# SparkX_EZ_ARTIC_R2.net
KiCad netlist of a schematic drawn in EAGLE
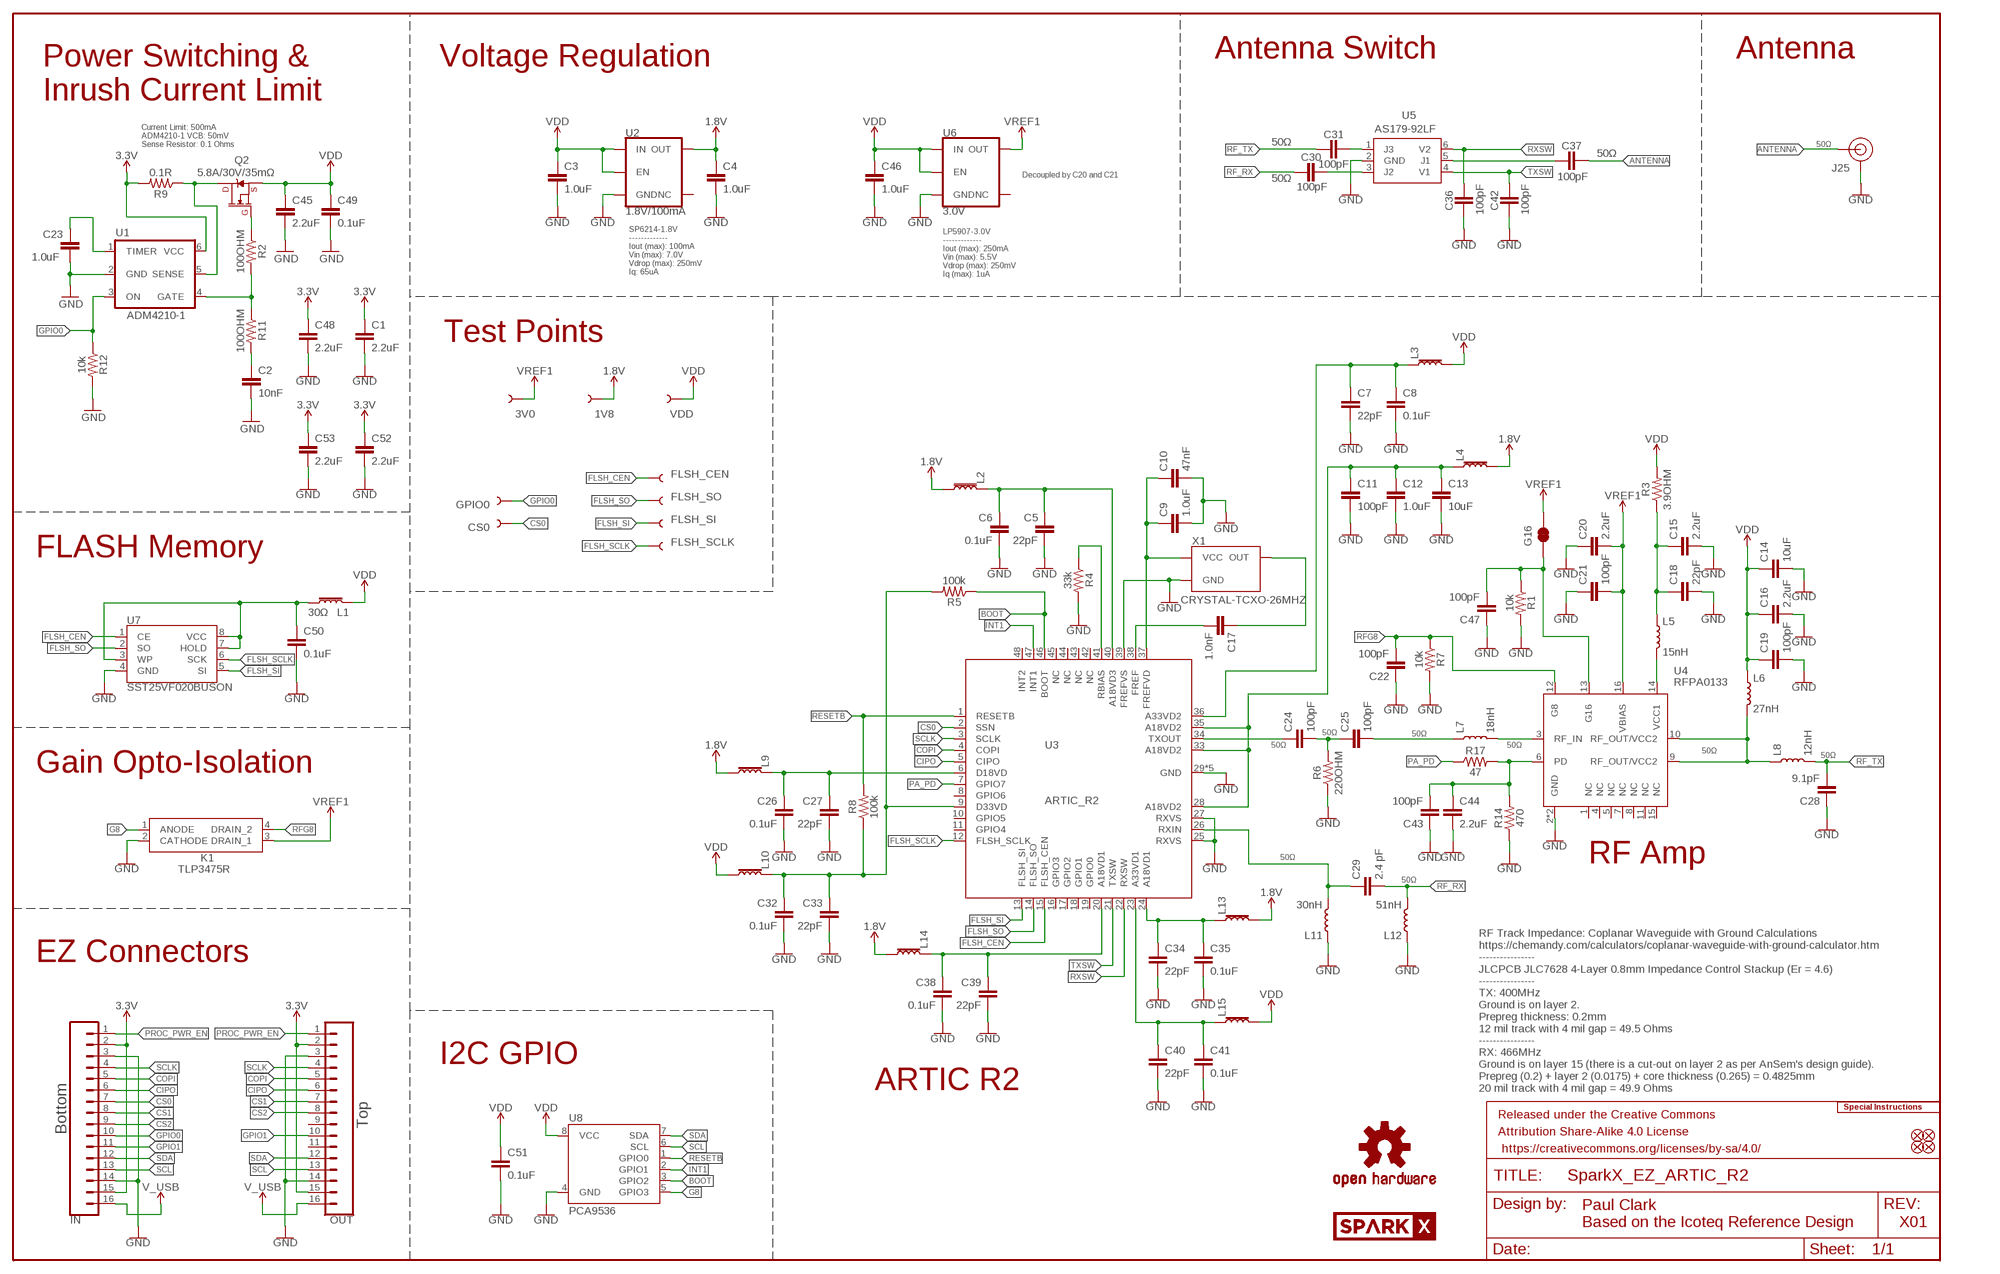
[diagram p0: schematic, sheet 1]

(export (version "E")
  (design (tool "Eeschema 10.0.6"))
  (components
    (comp (ref "1V8")
      (value "TEST-POINT3")
      (footprint "eagle-import:PAD.03X.03")
      (libsource (lib "eagle-import") (part "TEST-POINT3"))
    )
    (comp (ref "3V0")
      (value "TEST-POINT3")
      (footprint "eagle-import:PAD.03X.03")
      (libsource (lib "eagle-import") (part "TEST-POINT3"))
    )
    (comp (ref "C1")
      (value "2.2uF")
      (footprint "eagle-import:0402-TIGHT")
      (libsource (lib "eagle-import") (part "2.2UF-0402_TIGHT-10V-10%-X5R"))
    )
    (comp (ref "C2")
      (value "10nF")
      (footprint "eagle-import:0402-TIGHT")
      (libsource (lib "eagle-import") (part "10NF-0402T-25V-10%"))
    )
    (comp (ref "C3")
      (value "1.0uF")
      (footprint "eagle-import:0402-TIGHT")
      (libsource (lib "eagle-import") (part "1.0UF-0402T-16V-10%"))
    )
    (comp (ref "C4")
      (value "1.0uF")
      (footprint "eagle-import:0402-TIGHT")
      (libsource (lib "eagle-import") (part "1.0UF-0402T-16V-10%"))
    )
    (comp (ref "C5")
      (value "22pF")
      (footprint "eagle-import:0402-TIGHT")
      (libsource (lib "eagle-import") (part "22PF-0402T-16V-10%"))
    )
    (comp (ref "C6")
      (value "0.1uF")
      (footprint "eagle-import:0402-TIGHT")
      (libsource (lib "eagle-import") (part "0.1UF-0402T-6.3V-10%-X7R"))
    )
    (comp (ref "C7")
      (value "22pF")
      (footprint "eagle-import:0402-TIGHT")
      (libsource (lib "eagle-import") (part "22PF-0402T-16V-10%"))
    )
    (comp (ref "C8")
      (value "0.1uF")
      (footprint "eagle-import:0402-TIGHT")
      (libsource (lib "eagle-import") (part "0.1UF-0402T-6.3V-10%-X7R"))
    )
    (comp (ref "C9")
      (value "1.0uF")
      (footprint "eagle-import:0402-TIGHT")
      (libsource (lib "eagle-import") (part "1.0UF-0402T-16V-10%"))
    )
    (comp (ref "C10")
      (value "47nF")
      (footprint "eagle-import:0402-TIGHT")
      (libsource (lib "eagle-import") (part "47NF-0402_TIGHT-25V-10%-X7R"))
    )
    (comp (ref "C11")
      (value "100pF")
      (footprint "eagle-import:0402-TIGHT")
      (libsource (lib "eagle-import") (part "100PF-0402T-50V-5%"))
    )
    (comp (ref "C12")
      (value "1.0uF")
      (footprint "eagle-import:0402-TIGHT")
      (libsource (lib "eagle-import") (part "1.0UF-0402T-16V-10%"))
    )
    (comp (ref "C13")
      (value "10uF")
      (footprint "eagle-import:0402-TIGHT")
      (libsource (lib "eagle-import") (part "10UF-0402T-6.3V-20%"))
    )
    (comp (ref "C14")
      (value "10uF")
      (footprint "eagle-import:0402-TIGHT")
      (libsource (lib "eagle-import") (part "10UF-0402T-6.3V-20%"))
    )
    (comp (ref "C15")
      (value "2.2uF")
      (footprint "eagle-import:0402-TIGHT")
      (libsource (lib "eagle-import") (part "2.2UF-0402_TIGHT-10V-10%-X5R"))
    )
    (comp (ref "C16")
      (value "2.2uF")
      (footprint "eagle-import:0402-TIGHT")
      (libsource (lib "eagle-import") (part "2.2UF-0402_TIGHT-10V-10%-X5R"))
    )
    (comp (ref "C17")
      (value "1.0nF")
      (footprint "eagle-import:0402-TIGHT")
      (libsource (lib "eagle-import") (part "1.0NF/1000PF-0402_TIGHT-50V-10%"))
    )
    (comp (ref "C18")
      (value "22pF")
      (footprint "eagle-import:0402-TIGHT")
      (libsource (lib "eagle-import") (part "22PF-0402T-16V-10%"))
    )
    (comp (ref "C19")
      (value "100pF")
      (footprint "eagle-import:0402-TIGHT")
      (libsource (lib "eagle-import") (part "100PF-0402T-50V-5%"))
    )
    (comp (ref "C20")
      (value "2.2uF")
      (footprint "eagle-import:0402-TIGHT")
      (libsource (lib "eagle-import") (part "2.2UF-0402_TIGHT-10V-10%-X5R"))
    )
    (comp (ref "C21")
      (value "100pF")
      (footprint "eagle-import:0402-TIGHT")
      (libsource (lib "eagle-import") (part "100PF-0402T-50V-5%"))
    )
    (comp (ref "C22")
      (value "100pF")
      (footprint "eagle-import:0402-TIGHT")
      (libsource (lib "eagle-import") (part "100PF-0402T-50V-5%"))
    )
    (comp (ref "C23")
      (value "1.0uF")
      (footprint "eagle-import:0402-TIGHT")
      (libsource (lib "eagle-import") (part "1.0UF-0402T-16V-10%"))
    )
    (comp (ref "C24")
      (value "100pF")
      (footprint "eagle-import:0402-TIGHT")
      (libsource (lib "eagle-import") (part "100PF-0402T-50V-5%"))
    )
    (comp (ref "C25")
      (value "100pF")
      (footprint "eagle-import:0402-TIGHT")
      (libsource (lib "eagle-import") (part "100PF-0402T-50V-5%"))
    )
    (comp (ref "C26")
      (value "0.1uF")
      (footprint "eagle-import:0402-TIGHT")
      (libsource (lib "eagle-import") (part "0.1UF-0402T-6.3V-10%-X7R"))
    )
    (comp (ref "C27")
      (value "22pF")
      (footprint "eagle-import:0402-TIGHT")
      (libsource (lib "eagle-import") (part "22PF-0402T-16V-10%"))
    )
    (comp (ref "C28")
      (value "9.1pF")
      (footprint "eagle-import:0402-TIGHT")
      (fields (field (name "MOUSER_PART") "609-500R07S9R1CV4T"))
      (libsource (lib "eagle-import") (part "9.1PF-0402-TIGHT"))
    )
    (comp (ref "C29")
      (value "2.4 pF")
      (footprint "eagle-import:0402_MURATA")
      (libsource (lib "eagle-import") (part "2.4PF-0402"))
    )
    (comp (ref "C30")
      (value "100pF")
      (footprint "eagle-import:0402-TIGHT")
      (libsource (lib "eagle-import") (part "100PF-0402T-50V-5%"))
    )
    (comp (ref "C31")
      (value "100pF")
      (footprint "eagle-import:0402-TIGHT")
      (libsource (lib "eagle-import") (part "100PF-0402T-50V-5%"))
    )
    (comp (ref "C32")
      (value "0.1uF")
      (footprint "eagle-import:0402-TIGHT")
      (libsource (lib "eagle-import") (part "0.1UF-0402T-6.3V-10%-X7R"))
    )
    (comp (ref "C33")
      (value "22pF")
      (footprint "eagle-import:0402-TIGHT")
      (libsource (lib "eagle-import") (part "22PF-0402T-16V-10%"))
    )
    (comp (ref "C34")
      (value "22pF")
      (footprint "eagle-import:0402-TIGHT")
      (libsource (lib "eagle-import") (part "22PF-0402T-16V-10%"))
    )
    (comp (ref "C35")
      (value "0.1uF")
      (footprint "eagle-import:0402-TIGHT")
      (libsource (lib "eagle-import") (part "0.1UF-0402T-6.3V-10%-X7R"))
    )
    (comp (ref "C36")
      (value "100pF")
      (footprint "eagle-import:0402-TIGHT")
      (libsource (lib "eagle-import") (part "100PF-0402T-50V-5%"))
    )
    (comp (ref "C37")
      (value "100pF")
      (footprint "eagle-import:0402-TIGHT")
      (libsource (lib "eagle-import") (part "100PF-0402T-50V-5%"))
    )
    (comp (ref "C38")
      (value "0.1uF")
      (footprint "eagle-import:0402-TIGHT")
      (libsource (lib "eagle-import") (part "0.1UF-0402T-6.3V-10%-X7R"))
    )
    (comp (ref "C39")
      (value "22pF")
      (footprint "eagle-import:0402-TIGHT")
      (libsource (lib "eagle-import") (part "22PF-0402T-16V-10%"))
    )
    (comp (ref "C40")
      (value "22pF")
      (footprint "eagle-import:0402-TIGHT")
      (libsource (lib "eagle-import") (part "22PF-0402T-16V-10%"))
    )
    (comp (ref "C41")
      (value "0.1uF")
      (footprint "eagle-import:0402-TIGHT")
      (libsource (lib "eagle-import") (part "0.1UF-0402T-6.3V-10%-X7R"))
    )
    (comp (ref "C42")
      (value "100pF")
      (footprint "eagle-import:0402-TIGHT")
      (libsource (lib "eagle-import") (part "100PF-0402T-50V-5%"))
    )
    (comp (ref "C43")
      (value "100pF")
      (footprint "eagle-import:0402-TIGHT")
      (libsource (lib "eagle-import") (part "100PF-0402T-50V-5%"))
    )
    (comp (ref "C44")
      (value "2.2uF")
      (footprint "eagle-import:0402-TIGHT")
      (libsource (lib "eagle-import") (part "2.2UF-0402_TIGHT-10V-10%-X5R"))
    )
    (comp (ref "C45")
      (value "2.2uF")
      (footprint "eagle-import:0402-TIGHT")
      (libsource (lib "eagle-import") (part "2.2UF-0402_TIGHT-10V-10%-X5R"))
    )
    (comp (ref "C46")
      (value "1.0uF")
      (footprint "eagle-import:0402-TIGHT")
      (libsource (lib "eagle-import") (part "1.0UF-0402T-16V-10%"))
    )
    (comp (ref "C47")
      (value "100pF")
      (footprint "eagle-import:0402-TIGHT")
      (libsource (lib "eagle-import") (part "100PF-0402T-50V-5%"))
    )
    (comp (ref "C48")
      (value "2.2uF")
      (footprint "eagle-import:0402-TIGHT")
      (libsource (lib "eagle-import") (part "2.2UF-0402_TIGHT-10V-10%-X5R"))
    )
    (comp (ref "C49")
      (value "0.1uF")
      (footprint "eagle-import:0402-TIGHT")
      (libsource (lib "eagle-import") (part "0.1UF-0402T-10V-10%-X7R"))
    )
    (comp (ref "C50")
      (value "0.1uF")
      (footprint "eagle-import:0402-TIGHT")
      (libsource (lib "eagle-import") (part "0.1UF-0402T-6.3V-10%-X7R"))
    )
    (comp (ref "C51")
      (value "0.1uF")
      (footprint "eagle-import:0402-TIGHT")
      (libsource (lib "eagle-import") (part "0.1UF-0402T-10V-10%-X7R"))
    )
    (comp (ref "C52")
      (value "2.2uF")
      (footprint "eagle-import:0402-TIGHT")
      (libsource (lib "eagle-import") (part "2.2UF-0402_TIGHT-10V-10%-X5R"))
    )
    (comp (ref "C53")
      (value "2.2uF")
      (footprint "eagle-import:0402-TIGHT")
      (libsource (lib "eagle-import") (part "2.2UF-0402_TIGHT-10V-10%-X5R"))
    )
    (comp (ref "CS0")
      (value "TEST-POINT3")
      (footprint "eagle-import:PAD.03X.03")
      (libsource (lib "eagle-import") (part "TEST-POINT3"))
    )
    (comp (ref "FD1")
      (value "FIDUCIALUFIDUCIAL")
      (footprint "eagle-import:FIDUCIAL-MICRO")
      (libsource (lib "eagle-import") (part "FIDUCIALUFIDUCIAL"))
    )
    (comp (ref "FD2")
      (value "FIDUCIALUFIDUCIAL")
      (footprint "eagle-import:FIDUCIAL-MICRO")
      (libsource (lib "eagle-import") (part "FIDUCIALUFIDUCIAL"))
    )
    (comp (ref "FD3")
      (value "FIDUCIALUFIDUCIAL")
      (footprint "eagle-import:FIDUCIAL-MICRO")
      (libsource (lib "eagle-import") (part "FIDUCIALUFIDUCIAL"))
    )
    (comp (ref "FD4")
      (value "FIDUCIALUFIDUCIAL")
      (footprint "eagle-import:FIDUCIAL-MICRO")
      (libsource (lib "eagle-import") (part "FIDUCIALUFIDUCIAL"))
    )
    (comp (ref "FLSH_CEN")
      (value "TEST-POINT3")
      (footprint "eagle-import:PAD.03X.03")
      (libsource (lib "eagle-import") (part "TEST-POINT3"))
    )
    (comp (ref "FLSH_SCLK")
      (value "TEST-POINT3")
      (footprint "eagle-import:PAD.03X.03")
      (libsource (lib "eagle-import") (part "TEST-POINT3"))
    )
    (comp (ref "FLSH_SI")
      (value "TEST-POINT3")
      (footprint "eagle-import:PAD.03X.03")
      (libsource (lib "eagle-import") (part "TEST-POINT3"))
    )
    (comp (ref "FLSH_SO")
      (value "TEST-POINT3")
      (footprint "eagle-import:PAD.03X.03")
      (libsource (lib "eagle-import") (part "TEST-POINT3"))
    )
    (comp (ref "FRAME1")
      (value "FRAME-LEDGER")
      (footprint "eagle-import:CREATIVE_COMMONS")
      (libsource (lib "eagle-import") (part "FRAME-LEDGER"))
    )
    (comp (ref "G16")
      (value "JUMPER-SMT_2_NC_TRACE_NO-SILK")
      (footprint "eagle-import:SMT-JUMPER_2_NC_TRACE_NO-SILK")
      (libsource (lib "eagle-import") (part "JUMPER-SMT_2_NC_TRACE_NO-SILK"))
    )
    (comp (ref "GPIO0")
      (value "TEST-POINT3")
      (footprint "eagle-import:PAD.03X.03")
      (libsource (lib "eagle-import") (part "TEST-POINT3"))
    )
    (comp (ref "IN")
      (value "CONN_16FPC_16_0.5MM")
      (footprint "eagle-import:FPC_16_0.5MM")
      (libsource (lib "eagle-import") (part "CONN_16FPC_16_0.5MM"))
    )
    (comp (ref "J25")
      (value "U.FL")
      (footprint "eagle-import:U.FL_REDUCED_FOOTPRINT")
      (libsource (lib "eagle-import") (part "U.FL2PIN_REDUCED_FOOTPRINT"))
    )
    (comp (ref "K1")
      (value "TLP3475R")
      (footprint "eagle-import:TLP3475RTPF")
      (fields
        (field (name "DIGIKEY_PART") "TLP3475R(TPFCT-ND - Cut Tape (CT)")
        (field (name "MOUSER_PART_NUMBER") "757-TLP3475RTPF")
      )
      (libsource (lib "eagle-import") (part "TLP3475R"))
    )
    (comp (ref "L1")
      (value "30Ω")
      (footprint "eagle-import:0402-TIGHT")
      (libsource (lib "eagle-import") (part "FERRITE_BEAD-0402-30OHM-100MHZ"))
    )
    (comp (ref "L2")
      (value "30Ω")
      (footprint "eagle-import:0402-TIGHT")
      (libsource (lib "eagle-import") (part "FERRITE_BEAD-0402-30OHM-100MHZ"))
    )
    (comp (ref "L3")
      (value "30Ω")
      (footprint "eagle-import:0402-TIGHT")
      (libsource (lib "eagle-import") (part "FERRITE_BEAD-0402-30OHM-100MHZ"))
    )
    (comp (ref "L4")
      (value "30Ω")
      (footprint "eagle-import:0402-TIGHT")
      (libsource (lib "eagle-import") (part "FERRITE_BEAD-0402-30OHM-100MHZ"))
    )
    (comp (ref "L5")
      (value "15nH")
      (footprint "eagle-import:0402_COILCRAFT")
      (fields (field (name "MOUSER_PART") "994-0402HP-15NXGLU"))
      (libsource (lib "eagle-import") (part "15NH-0402"))
    )
    (comp (ref "L6")
      (value "27nH")
      (footprint "eagle-import:0402_COILCRAFT")
      (fields (field (name "MOUSER_PART") "994-0402HP-27NXGLU"))
      (libsource (lib "eagle-import") (part "27NH-0402"))
    )
    (comp (ref "L7")
      (value "18nH")
      (footprint "eagle-import:0402_COILCRAFT")
      (fields (field (name "MOUSER_PART") "994-0402HP-18NXGLU"))
      (libsource (lib "eagle-import") (part "18NH-0402"))
    )
    (comp (ref "L8")
      (value "12nH")
      (footprint "eagle-import:0402_COILCRAFT")
      (fields (field (name "MOUSER_PART") "994-0402HP-12NXGLU"))
      (libsource (lib "eagle-import") (part "12NH-0402"))
    )
    (comp (ref "L9")
      (value "30Ω")
      (footprint "eagle-import:0402-TIGHT")
      (libsource (lib "eagle-import") (part "FERRITE_BEAD-0402-30OHM-100MHZ"))
    )
    (comp (ref "L10")
      (value "30Ω")
      (footprint "eagle-import:0402-TIGHT")
      (libsource (lib "eagle-import") (part "FERRITE_BEAD-0402-30OHM-100MHZ"))
    )
    (comp (ref "L11")
      (value "30nH")
      (footprint "eagle-import:0402_COILCRAFT")
      (fields (field (name "MOUSER_PART") "994-0402HP-30NXGLU"))
      (libsource (lib "eagle-import") (part "30NH-0402"))
    )
    (comp (ref "L12")
      (value "51nH")
      (footprint "eagle-import:0402_COILCRAFT")
      (fields (field (name "MOUSER_PART") "994-0402HP-51NXGLU"))
      (libsource (lib "eagle-import") (part "51NH-0402"))
    )
    (comp (ref "L13")
      (value "30Ω")
      (footprint "eagle-import:0402-TIGHT")
      (libsource (lib "eagle-import") (part "FERRITE_BEAD-0402-30OHM-100MHZ"))
    )
    (comp (ref "L14")
      (value "30Ω")
      (footprint "eagle-import:0402-TIGHT")
      (libsource (lib "eagle-import") (part "FERRITE_BEAD-0402-30OHM-100MHZ"))
    )
    (comp (ref "L15")
      (value "30Ω")
      (footprint "eagle-import:0402-TIGHT")
      (libsource (lib "eagle-import") (part "FERRITE_BEAD-0402-30OHM-100MHZ"))
    )
    (comp (ref "LOGO1")
      (value "SPECIAL_INSTRUCTIONS-ORDERING")
      (footprint "eagle-import:ORDERING_INSTRUCTIONS")
      (libsource (lib "eagle-import") (part "SPECIAL_INSTRUCTIONS-ORDERING"))
    )
    (comp (ref "LOGO2")
      (value "OSHW-LOGOMINI")
      (footprint "eagle-import:OSHW-LOGO-MINI")
      (libsource (lib "eagle-import") (part "OSHW-LOGOMINI"))
    )
    (comp (ref "LOGO3")
      (value "OSHW-LOGOMINI")
      (footprint "eagle-import:OSHW-LOGO-MINI")
      (libsource (lib "eagle-import") (part "OSHW-LOGOMINI"))
    )
    (comp (ref "OUT")
      (value "CONN_16FPC_16_0.5MM")
      (footprint "eagle-import:FPC_16_0.5MM")
      (libsource (lib "eagle-import") (part "CONN_16FPC_16_0.5MM"))
    )
    (comp (ref "Q2")
      (value "5.8A/30V/35mΩ")
      (footprint "eagle-import:SOT23-3")
      (libsource (lib "eagle-import") (part "MOSFET-NCH-AO3404A"))
    )
    (comp (ref "R1")
      (value "10k")
      (footprint "eagle-import:0402-TIGHT")
      (libsource (lib "eagle-import") (part "10KOHM-0402T-1/16W-1%"))
    )
    (comp (ref "R2")
      (value "100OHM")
      (footprint "eagle-import:0402-TIGHT")
      (libsource (lib "eagle-import") (part "100OHM"))
    )
    (comp (ref "R3")
      (value "3.9OHM")
      (footprint "eagle-import:0402-TIGHT")
      (fields (field (name "MOUSER_PART") "603-RC0402FR-073R9L"))
      (libsource (lib "eagle-import") (part "3.9OHM"))
    )
    (comp (ref "R4")
      (value "33k")
      (footprint "eagle-import:0402-TIGHT")
      (libsource (lib "eagle-import") (part "33KOHM-0402T-1/16W-1%"))
    )
    (comp (ref "R5")
      (value "100k")
      (footprint "eagle-import:0402-TIGHT")
      (libsource (lib "eagle-import") (part "100KOHM-0402T-1/16W-1%"))
    )
    (comp (ref "R6")
      (value "220OHM")
      (footprint "eagle-import:0402-TIGHT")
      (fields (field (name "MOUSER_PART") "755-SFR01MZPF2200"))
      (libsource (lib "eagle-import") (part "220OHM"))
    )
    (comp (ref "R7")
      (value "10k")
      (footprint "eagle-import:0402-TIGHT")
      (libsource (lib "eagle-import") (part "10KOHM-0402T-1/16W-1%"))
    )
    (comp (ref "R8")
      (value "100k")
      (footprint "eagle-import:0402-TIGHT")
      (libsource (lib "eagle-import") (part "100KOHM-0402T-1/16W-1%"))
    )
    (comp (ref "R9")
      (value "0.1R")
      (footprint "eagle-import:0603")
      (fields (field (name "DIGIKEY_PART") "P17478CT-ND") (field (name "MANUFACTURER_PART") "ERJ-3BWFR100V"))
      (libsource (lib "eagle-import") (part "RESISTOR_0603_100MILLIOHM0603"))
    )
    (comp (ref "R11")
      (value "100OHM")
      (footprint "eagle-import:0402-TIGHT")
      (libsource (lib "eagle-import") (part "100OHM"))
    )
    (comp (ref "R12")
      (value "10k")
      (footprint "eagle-import:0402-TIGHT")
      (libsource (lib "eagle-import") (part "10KOHM-0402T-1/16W-1%"))
    )
    (comp (ref "R14")
      (value "470")
      (footprint "eagle-import:0402-TIGHT")
      (libsource (lib "eagle-import") (part "470OHM-0402-TIGHT-1/16W-1%"))
    )
    (comp (ref "R17")
      (value "47")
      (footprint "eagle-import:0402-TIGHT")
      (libsource (lib "eagle-import") (part "47OHM-0402-TIGHT-1/16W-1%"))
    )
    (comp (ref "U$4")
      (value "SPARKX-LOGO3")
      (footprint "eagle-import:SPARKX-SMALL")
      (libsource (lib "eagle-import") (part "SPARKX-LOGO3"))
    )
    (comp (ref "U$8")
      (value "SPARKX-LOGO2")
      (footprint "eagle-import:SPARKX-TINY")
      (libsource (lib "eagle-import") (part "SPARKX-LOGO2"))
    )
    (comp (ref "U1")
      (value "ADM4210-1")
      (footprint "eagle-import:TSOT6")
      (libsource (lib "eagle-import") (part "ADM4210-1"))
    )
    (comp (ref "U2")
      (value "1.8V/100mA")
      (footprint "eagle-import:SC70")
      (libsource (lib "eagle-import") (part "V_REG_SP6214-1.8V"))
    )
    (comp (ref "U3")
      (value "ARTIC_R2")
      (footprint "eagle-import:QFN-48")
      (libsource (lib "eagle-import") (part "ARTIC_R2"))
    )
    (comp (ref "U4")
      (value "RFPA0133")
      (footprint "eagle-import:QFN50P300X300X86-17N")
      (fields
        (field (name "MANUFACTURER_PART_NUMBER") "RFPA0133TR7")
        (field (name "MOUSER_PART_NUMBER") "772-RFPA0133")
      )
      (libsource (lib "eagle-import") (part "RFPA0133"))
    )
    (comp (ref "U5")
      (value "AS179-92LF")
      (footprint "eagle-import:SOT65P220X100-6N")
      (libsource (lib "eagle-import") (part "AS179-92LF"))
    )
    (comp (ref "U6")
      (value "3.0V")
      (footprint "eagle-import:SOT23-5")
      (fields
        (field (name "DIGIKEY_PART") "296-40357-1-ND")
        (field (name "MANU_PART") "LP5907MFX-3.0/NOPB")
        (field (name "MOUSER_PART") "595-LP5907MFX-3.0NPB")
      )
      (libsource (lib "eagle-import") (part "V_REG_LP5907SOT23-3.0V"))
    )
    (comp (ref "U7")
      (value "SST25VF020BUSON")
      (footprint "eagle-import:USON_3X2MM")
      (fields
        (field (name "DIGIKEY_PART") "SST25VF020B-80-4I-Q3AE-TCT-ND")
        (field (name "MANU_PART") "SST25VF020B-80-4I-Q3AE-T")
      )
      (libsource (lib "eagle-import") (part "SST25VF020BUSON"))
    )
    (comp (ref "U8")
      (value "PCA9536")
      (footprint "eagle-import:MSOP8")
      (libsource (lib "eagle-import") (part "PCA9536"))
    )
    (comp (ref "VDD")
      (value "TEST-POINT3")
      (footprint "eagle-import:PAD.03X.03")
      (libsource (lib "eagle-import") (part "TEST-POINT3"))
    )
    (comp (ref "X1")
      (value "CRYSTAL-TCXO-26MHZ")
      (footprint "eagle-import:CRYSTAL-TCXO-SMD-1.65X1.25")
      (fields (field (name "MOUSER_PART") "449-LFTCXO073004CUTT"))
      (libsource (lib "eagle-import") (part "CRYSTAL-TCXO-26MHZ"))
    )
  )
  (nets
    (net (code "1") (name "1.8V") (class "Default")
      (node (ref "1V8") (pin "1") (pinfunction "1_1") (pintype "bidirectional"))
      (node (ref "C4") (pin "1") (pinfunction "1_1") (pintype "passive"))
      (node (ref "L13") (pin "2") (pinfunction "2_2") (pintype "passive"))
      (node (ref "L14") (pin "2") (pinfunction "2_2") (pintype "passive"))
      (node (ref "L2") (pin "2") (pinfunction "2_2") (pintype "passive"))
      (node (ref "L4") (pin "2") (pinfunction "2_2") (pintype "passive"))
      (node (ref "L9") (pin "2") (pinfunction "2_2") (pintype "passive"))
      (node (ref "U2") (pin "5") (pinfunction "OUT_5") (pintype "passive"))
    )
    (net (code "2") (name "3.3V") (class "Default")
      (node (ref "C1") (pin "1") (pinfunction "1_1") (pintype "passive"))
      (node (ref "C48") (pin "1") (pinfunction "1_1") (pintype "passive"))
      (node (ref "C52") (pin "1") (pinfunction "1_1") (pintype "passive"))
      (node (ref "C53") (pin "1") (pinfunction "1_1") (pintype "passive"))
      (node (ref "IN") (pin "15") (pinfunction "15_15") (pintype "passive"))
      (node (ref "IN") (pin "2") (pinfunction "2_2") (pintype "passive"))
      (node (ref "OUT") (pin "15") (pinfunction "15_15") (pintype "passive"))
      (node (ref "OUT") (pin "2") (pinfunction "2_2") (pintype "passive"))
      (node (ref "R9") (pin "2") (pinfunction "2_2") (pintype "passive"))
      (node (ref "U1") (pin "6") (pinfunction "VCC_6") (pintype "power_in"))
    )
    (net (code "3") (name "ANTENNA") (class "Default")
      (node (ref "C37") (pin "1") (pinfunction "1_1") (pintype "passive"))
      (node (ref "J25") (pin "FEED") (pinfunction "SIGNAL_FEED") (pintype "bidirectional"))
    )
    (net (code "4") (name "BOOT") (class "Default")
      (node (ref "R5") (pin "1") (pinfunction "1_1") (pintype "passive"))
      (node (ref "U3") (pin "46") (pinfunction "BOOT_46") (pintype "bidirectional"))
      (node (ref "U8") (pin "3") (pinfunction "GPIO2_3") (pintype "bidirectional"))
    )
    (net (code "5") (name "CIPO") (class "Default")
      (node (ref "IN") (pin "6") (pinfunction "6_6") (pintype "passive"))
      (node (ref "OUT") (pin "6") (pinfunction "6_6") (pintype "passive"))
      (node (ref "U3") (pin "5") (pinfunction "CIPO_5") (pintype "bidirectional"))
    )
    (net (code "6") (name "COPI") (class "Default")
      (node (ref "IN") (pin "5") (pinfunction "5_5") (pintype "passive"))
      (node (ref "OUT") (pin "5") (pinfunction "5_5") (pintype "passive"))
      (node (ref "U3") (pin "4") (pinfunction "COPI_4") (pintype "bidirectional"))
    )
    (net (code "7") (name "CS0") (class "Default")
      (node (ref "CS0") (pin "1") (pinfunction "1_1") (pintype "bidirectional"))
      (node (ref "IN") (pin "7") (pinfunction "7_7") (pintype "passive"))
      (node (ref "U3") (pin "2") (pinfunction "SSN_2") (pintype "bidirectional"))
    )
    (net (code "8") (name "CS1") (class "Default")
      (node (ref "IN") (pin "8") (pinfunction "8_8") (pintype "passive"))
      (node (ref "OUT") (pin "7") (pinfunction "7_7") (pintype "passive"))
    )
    (net (code "9") (name "CS2") (class "Default")
      (node (ref "IN") (pin "9") (pinfunction "9_9") (pintype "passive"))
      (node (ref "OUT") (pin "8") (pinfunction "8_8") (pintype "passive"))
    )
    (net (code "10") (name "FLSH_CEN") (class "Default")
      (node (ref "FLSH_CEN") (pin "1") (pinfunction "1_1") (pintype "bidirectional"))
      (node (ref "U3") (pin "15") (pinfunction "FLSH_CEN_15") (pintype "bidirectional"))
      (node (ref "U7") (pin "1") (pinfunction "CE_1") (pintype "bidirectional"))
    )
    (net (code "11") (name "FLSH_SCLK") (class "Default")
      (node (ref "FLSH_SCLK") (pin "1") (pinfunction "1_1") (pintype "bidirectional"))
      (node (ref "U3") (pin "12") (pinfunction "FLSH_SCLK_12") (pintype "bidirectional"))
      (node (ref "U7") (pin "6") (pinfunction "SCK_6") (pintype "bidirectional"))
    )
    (net (code "12") (name "FLSH_SI") (class "Default")
      (node (ref "FLSH_SI") (pin "1") (pinfunction "1_1") (pintype "bidirectional"))
      (node (ref "U3") (pin "13") (pinfunction "FLSH_SI_13") (pintype "bidirectional"))
      (node (ref "U7") (pin "5") (pinfunction "SI_5") (pintype "bidirectional"))
    )
    (net (code "13") (name "FLSH_SO") (class "Default")
      (node (ref "FLSH_SO") (pin "1") (pinfunction "1_1") (pintype "bidirectional"))
      (node (ref "U3") (pin "14") (pinfunction "FLSH_SO_14") (pintype "bidirectional"))
      (node (ref "U7") (pin "2") (pinfunction "SO_2") (pintype "bidirectional"))
    )
    (net (code "14") (name "G8") (class "Default")
      (node (ref "K1") (pin "1") (pinfunction "ANODE_1") (pintype "bidirectional"))
      (node (ref "U8") (pin "5") (pinfunction "GPIO3_5") (pintype "bidirectional"))
    )
    (net (code "15") (name "GND") (class "Default")
      (node (ref "C1") (pin "2") (pinfunction "2_2") (pintype "passive"))
      (node (ref "C10") (pin "2") (pinfunction "2_2") (pintype "passive"))
      (node (ref "C11") (pin "2") (pinfunction "2_2") (pintype "passive"))
      (node (ref "C12") (pin "2") (pinfunction "2_2") (pintype "passive"))
      (node (ref "C13") (pin "2") (pinfunction "2_2") (pintype "passive"))
      (node (ref "C14") (pin "2") (pinfunction "2_2") (pintype "passive"))
      (node (ref "C15") (pin "2") (pinfunction "2_2") (pintype "passive"))
      (node (ref "C16") (pin "2") (pinfunction "2_2") (pintype "passive"))
      (node (ref "C18") (pin "2") (pinfunction "2_2") (pintype "passive"))
      (node (ref "C19") (pin "2") (pinfunction "2_2") (pintype "passive"))
      (node (ref "C2") (pin "2") (pinfunction "2_2") (pintype "passive"))
      (node (ref "C20") (pin "1") (pinfunction "1_1") (pintype "passive"))
      (node (ref "C21") (pin "1") (pinfunction "1_1") (pintype "passive"))
      (node (ref "C22") (pin "1") (pinfunction "1_1") (pintype "passive"))
      (node (ref "C23") (pin "2") (pinfunction "2_2") (pintype "passive"))
      (node (ref "C26") (pin "2") (pinfunction "2_2") (pintype "passive"))
      (node (ref "C27") (pin "2") (pinfunction "2_2") (pintype "passive"))
      (node (ref "C28") (pin "1") (pinfunction "1_1") (pintype "passive"))
      (node (ref "C3") (pin "2") (pinfunction "2_2") (pintype "passive"))
      (node (ref "C32") (pin "2") (pinfunction "2_2") (pintype "passive"))
      (node (ref "C33") (pin "2") (pinfunction "2_2") (pintype "passive"))
      (node (ref "C34") (pin "2") (pinfunction "2_2") (pintype "passive"))
      (node (ref "C35") (pin "2") (pinfunction "2_2") (pintype "passive"))
      (node (ref "C36") (pin "2") (pinfunction "2_2") (pintype "passive"))
      (node (ref "C38") (pin "2") (pinfunction "2_2") (pintype "passive"))
      (node (ref "C39") (pin "2") (pinfunction "2_2") (pintype "passive"))
      (node (ref "C4") (pin "2") (pinfunction "2_2") (pintype "passive"))
      (node (ref "C40") (pin "2") (pinfunction "2_2") (pintype "passive"))
      (node (ref "C41") (pin "2") (pinfunction "2_2") (pintype "passive"))
      (node (ref "C42") (pin "2") (pinfunction "2_2") (pintype "passive"))
      (node (ref "C43") (pin "1") (pinfunction "1_1") (pintype "passive"))
      (node (ref "C44") (pin "2") (pinfunction "2_2") (pintype "passive"))
      (node (ref "C45") (pin "2") (pinfunction "2_2") (pintype "passive"))
      (node (ref "C46") (pin "2") (pinfunction "2_2") (pintype "passive"))
      (node (ref "C47") (pin "1") (pinfunction "1_1") (pintype "passive"))
      (node (ref "C48") (pin "2") (pinfunction "2_2") (pintype "passive"))
      (node (ref "C49") (pin "2") (pinfunction "2_2") (pintype "passive"))
      (node (ref "C5") (pin "2") (pinfunction "2_2") (pintype "passive"))
      (node (ref "C50") (pin "2") (pinfunction "2_2") (pintype "passive"))
      (node (ref "C51") (pin "2") (pinfunction "2_2") (pintype "passive"))
      (node (ref "C52") (pin "2") (pinfunction "2_2") (pintype "passive"))
      (node (ref "C53") (pin "2") (pinfunction "2_2") (pintype "passive"))
      (node (ref "C6") (pin "2") (pinfunction "2_2") (pintype "passive"))
      (node (ref "C7") (pin "2") (pinfunction "2_2") (pintype "passive"))
      (node (ref "C8") (pin "2") (pinfunction "2_2") (pintype "passive"))
      (node (ref "C9") (pin "2") (pinfunction "2_2") (pintype "passive"))
      (node (ref "IN") (pin "14") (pinfunction "14_14") (pintype "passive"))
      (node (ref "IN") (pin "3") (pinfunction "3_3") (pintype "passive"))
      (node (ref "J25") (pin "1") (pinfunction "GND_1") (pintype "bidirectional"))
      (node (ref "J25") (pin "2") (pinfunction "GND_2") (pintype "bidirectional"))
      (node (ref "K1") (pin "2") (pinfunction "CATHODE_2") (pintype "bidirectional"))
      (node (ref "L11") (pin "P$1") (pinfunction "1_P$1") (pintype "passive"))
      (node (ref "L12") (pin "P$1") (pinfunction "1_P$1") (pintype "passive"))
      (node (ref "OUT") (pin "14") (pinfunction "14_14") (pintype "passive"))
      (node (ref "OUT") (pin "3") (pinfunction "3_3") (pintype "passive"))
      (node (ref "R1") (pin "2") (pinfunction "2_2") (pintype "passive"))
      (node (ref "R12") (pin "2") (pinfunction "2_2") (pintype "passive"))
      (node (ref "R14") (pin "1") (pinfunction "1_1") (pintype "passive"))
      (node (ref "R4") (pin "2") (pinfunction "2_2") (pintype "passive"))
      (node (ref "R6") (pin "1") (pinfunction "1_1") (pintype "passive"))
      (node (ref "R7") (pin "2") (pinfunction "2_2") (pintype "passive"))
      (node (ref "U1") (pin "2") (pinfunction "GND_2") (pintype "power_in"))
      (node (ref "U2") (pin "2") (pinfunction "GND_2") (pintype "input"))
      (node (ref "U3") (pin "25") (pinfunction "RXVS_25") (pintype "bidirectional"))
      (node (ref "U3") (pin "27") (pinfunction "RXVS_27") (pintype "bidirectional"))
      (node (ref "U3") (pin "29") (pinfunction "GND_29") (pintype "bidirectional"))
      (node (ref "U3") (pin "30") (pinfunction "GND_30") (pintype "bidirectional"))
      (node (ref "U3") (pin "31") (pinfunction "GND_31") (pintype "bidirectional"))
      (node (ref "U3") (pin "32") (pinfunction "GND_32") (pintype "bidirectional"))
      (node (ref "U3") (pin "39") (pinfunction "FREFVS_39") (pintype "bidirectional"))
      (node (ref "U3") (pin "GND") (pinfunction "GND_GND") (pintype "bidirectional"))
      (node (ref "U4") (pin "2") (pinfunction "GND_2") (pintype "power_in"))
      (node (ref "U4") (pin "EDAP") (pinfunction "GND_EDAP") (pintype "power_in"))
      (node (ref "U5") (pin "2") (pinfunction "GND_2") (pintype "power_in"))
      (node (ref "U6") (pin "2") (pinfunction "GND_2") (pintype "input"))
      (node (ref "U7") (pin "4") (pinfunction "GND_4") (pintype "power_in"))
      (node (ref "U8") (pin "4") (pinfunction "GND_4") (pintype "bidirectional"))
      (node (ref "X1") (pin "1") (pinfunction "GND_1") (pintype "bidirectional"))
      (node (ref "X1") (pin "2") (pinfunction "GND_2") (pintype "bidirectional"))
    )
    (net (code "16") (name "GPIO0") (class "Default")
      (node (ref "GPIO0") (pin "1") (pinfunction "1_1") (pintype "bidirectional"))
      (node (ref "IN") (pin "10") (pinfunction "10_10") (pintype "passive"))
      (node (ref "R12") (pin "1") (pinfunction "1_1") (pintype "passive"))
      (node (ref "U1") (pin "3") (pinfunction "ON_3") (pintype "input"))
    )
    (net (code "17") (name "GPIO1") (class "Default")
      (node (ref "IN") (pin "11") (pinfunction "11_11") (pintype "passive"))
      (node (ref "OUT") (pin "10") (pinfunction "10_10") (pintype "passive"))
    )
    (net (code "18") (name "INT1") (class "Default")
      (node (ref "U3") (pin "47") (pinfunction "INT1_47") (pintype "bidirectional"))
      (node (ref "U8") (pin "2") (pinfunction "GPIO1_2") (pintype "bidirectional"))
    )
    (net (code "19") (name "Net-(C2-Pad1)") (class "Default")
      (node (ref "C2") (pin "1") (pinfunction "1_1") (pintype "passive"))
      (node (ref "R11") (pin "2") (pinfunction "2_2") (pintype "passive"))
    )
    (net (code "20") (name "Net-(C11-Pad1)") (class "Default")
      (node (ref "C11") (pin "1") (pinfunction "1_1") (pintype "passive"))
      (node (ref "C12") (pin "1") (pinfunction "1_1") (pintype "passive"))
      (node (ref "C13") (pin "1") (pinfunction "1_1") (pintype "passive"))
      (node (ref "L4") (pin "1") (pinfunction "1_1") (pintype "passive"))
      (node (ref "U3") (pin "28") (pinfunction "A18VD2_28") (pintype "power_in"))
      (node (ref "U3") (pin "33") (pinfunction "A18VD2_33") (pintype "power_in"))
      (node (ref "U3") (pin "35") (pinfunction "A18VD2_35") (pintype "power_in"))
    )
    (net (code "21") (name "Net-(C24-Pad2)") (class "Default")
      (node (ref "C24") (pin "2") (pinfunction "2_2") (pintype "passive"))
      (node (ref "C25") (pin "1") (pinfunction "1_1") (pintype "passive"))
      (node (ref "R6") (pin "2") (pinfunction "2_2") (pintype "passive"))
    )
    (net (code "22") (name "Net-(C29-1)") (class "Default")
      (node (ref "C29") (pin "P$1") (pinfunction "1_P$1") (pintype "passive"))
      (node (ref "L11") (pin "P$2") (pinfunction "2_P$2") (pintype "passive"))
      (node (ref "U3") (pin "26") (pinfunction "RXIN_26") (pintype "bidirectional"))
    )
    (net (code "23") (name "Net-(C34-Pad1)") (class "Default")
      (node (ref "C34") (pin "1") (pinfunction "1_1") (pintype "passive"))
      (node (ref "C35") (pin "1") (pinfunction "1_1") (pintype "passive"))
      (node (ref "L13") (pin "1") (pinfunction "1_1") (pintype "passive"))
      (node (ref "U3") (pin "24") (pinfunction "A18VD1_24") (pintype "power_in"))
    )
    (net (code "24") (name "Net-(C38-Pad1)") (class "Default")
      (node (ref "C38") (pin "1") (pinfunction "1_1") (pintype "passive"))
      (node (ref "C39") (pin "1") (pinfunction "1_1") (pintype "passive"))
      (node (ref "L14") (pin "1") (pinfunction "1_1") (pintype "passive"))
      (node (ref "U3") (pin "20") (pinfunction "A18VD1_20") (pintype "power_in"))
    )
    (net (code "25") (name "Net-(L5-1)") (class "Default")
      (node (ref "C15") (pin "1") (pinfunction "1_1") (pintype "passive"))
      (node (ref "C18") (pin "1") (pinfunction "1_1") (pintype "passive"))
      (node (ref "L5") (pin "P$1") (pinfunction "1_P$1") (pintype "passive"))
      (node (ref "R3") (pin "1") (pinfunction "1_1") (pintype "passive"))
    )
    (net (code "26") (name "Net-(L5-2)") (class "Default")
      (node (ref "L5") (pin "P$2") (pinfunction "2_P$2") (pintype "passive"))
      (node (ref "U4") (pin "14") (pinfunction "VCC1_14") (pintype "power_in"))
    )
    (net (code "27") (name "Net-(L6-2)") (class "Default")
      (node (ref "L6") (pin "P$2") (pinfunction "2_P$2") (pintype "passive"))
      (node (ref "L8") (pin "P$1") (pinfunction "1_P$1") (pintype "passive"))
      (node (ref "U4") (pin "10") (pinfunction "RF_OUT/VCC2_10") (pintype "output"))
      (node (ref "U4") (pin "9") (pinfunction "RF_OUT/VCC2_9") (pintype "output"))
    )
    (net (code "28") (name "Net-(L7-1)") (class "Default")
      (node (ref "C25") (pin "2") (pinfunction "2_2") (pintype "passive"))
      (node (ref "L7") (pin "P$1") (pinfunction "1_P$1") (pintype "passive"))
    )
    (net (code "29") (name "Net-(L7-2)") (class "Default")
      (node (ref "L7") (pin "P$2") (pinfunction "2_P$2") (pintype "passive"))
      (node (ref "U4") (pin "3") (pinfunction "RF_IN_3") (pintype "input"))
    )
    (net (code "30") (name "Net-(Q2-D)") (class "Default")
      (node (ref "Q2") (pin "3") (pinfunction "D_3") (pintype "bidirectional"))
      (node (ref "R9") (pin "1") (pinfunction "1_1") (pintype "passive"))
      (node (ref "U1") (pin "5") (pinfunction "SENSE_5") (pintype "input"))
    )
    (net (code "31") (name "Net-(Q2-G)") (class "Default")
      (node (ref "Q2") (pin "1") (pinfunction "G_1") (pintype "bidirectional"))
      (node (ref "R2") (pin "1") (pinfunction "1_1") (pintype "passive"))
    )
    (net (code "32") (name "Net-(U1-GATE)") (class "Default")
      (node (ref "R11") (pin "1") (pinfunction "1_1") (pintype "passive"))
      (node (ref "R2") (pin "2") (pinfunction "2_2") (pintype "passive"))
      (node (ref "U1") (pin "4") (pinfunction "GATE_4") (pintype "output"))
    )
    (net (code "33") (name "Net-(U1-TIMER)") (class "Default")
      (node (ref "C23") (pin "1") (pinfunction "1_1") (pintype "passive"))
      (node (ref "U1") (pin "1") (pinfunction "TIMER_1") (pintype "input"))
    )
    (net (code "34") (name "Net-(U3-A18VD3)") (class "Default")
      (node (ref "C5") (pin "1") (pinfunction "1_1") (pintype "passive"))
      (node (ref "C6") (pin "1") (pinfunction "1_1") (pintype "passive"))
      (node (ref "L2") (pin "1") (pinfunction "1_1") (pintype "passive"))
      (node (ref "U3") (pin "40") (pinfunction "A18VD3_40") (pintype "power_in"))
    )
    (net (code "35") (name "Net-(U3-A33VD1)") (class "Default")
      (node (ref "C40") (pin "1") (pinfunction "1_1") (pintype "passive"))
      (node (ref "C41") (pin "1") (pinfunction "1_1") (pintype "passive"))
      (node (ref "L15") (pin "1") (pinfunction "1_1") (pintype "passive"))
      (node (ref "U3") (pin "23") (pinfunction "A33VD1_23") (pintype "power_in"))
    )
    (net (code "36") (name "Net-(U3-A33VD2)") (class "Default")
      (node (ref "C7") (pin "1") (pinfunction "1_1") (pintype "passive"))
      (node (ref "C8") (pin "1") (pinfunction "1_1") (pintype "passive"))
      (node (ref "L3") (pin "1") (pinfunction "1_1") (pintype "passive"))
      (node (ref "U3") (pin "36") (pinfunction "A33VD2_36") (pintype "power_in"))
    )
    (net (code "37") (name "Net-(U3-D18VD)") (class "Default")
      (node (ref "C26") (pin "1") (pinfunction "1_1") (pintype "passive"))
      (node (ref "C27") (pin "1") (pinfunction "1_1") (pintype "passive"))
      (node (ref "L9") (pin "1") (pinfunction "1_1") (pintype "passive"))
      (node (ref "U3") (pin "6") (pinfunction "D18VD_6") (pintype "power_in"))
    )
    (net (code "38") (name "Net-(U3-D33VD)") (class "Default")
      (node (ref "C32") (pin "1") (pinfunction "1_1") (pintype "passive"))
      (node (ref "C33") (pin "1") (pinfunction "1_1") (pintype "passive"))
      (node (ref "L10") (pin "1") (pinfunction "1_1") (pintype "passive"))
      (node (ref "R5") (pin "2") (pinfunction "2_2") (pintype "passive"))
      (node (ref "R8") (pin "1") (pinfunction "1_1") (pintype "passive"))
      (node (ref "U3") (pin "9") (pinfunction "D33VD_9") (pintype "power_in"))
    )
    (net (code "39") (name "Net-(U3-FREF)") (class "Default")
      (node (ref "C17") (pin "2") (pinfunction "2_2") (pintype "passive"))
      (node (ref "U3") (pin "38") (pinfunction "FREF_38") (pintype "bidirectional"))
    )
    (net (code "40") (name "Net-(U3-FREFVD)") (class "Default")
      (node (ref "C10") (pin "1") (pinfunction "1_1") (pintype "passive"))
      (node (ref "C9") (pin "1") (pinfunction "1_1") (pintype "passive"))
      (node (ref "U3") (pin "37") (pinfunction "FREFVD_37") (pintype "bidirectional"))
      (node (ref "X1") (pin "4") (pinfunction "VCC_4") (pintype "bidirectional"))
    )
    (net (code "41") (name "Net-(U3-RBIAS)") (class "Default")
      (node (ref "R4") (pin "1") (pinfunction "1_1") (pintype "passive"))
      (node (ref "U3") (pin "41") (pinfunction "RBIAS_41") (pintype "bidirectional"))
    )
    (net (code "42") (name "Net-(U3-TXOUT)") (class "Default")
      (node (ref "C24") (pin "1") (pinfunction "1_1") (pintype "passive"))
      (node (ref "U3") (pin "34") (pinfunction "TXOUT_34") (pintype "bidirectional"))
    )
    (net (code "43") (name "Net-(U4-G16)") (class "Default")
      (node (ref "C47") (pin "2") (pinfunction "2_2") (pintype "passive"))
      (node (ref "G16") (pin "1") (pinfunction "1_1") (pintype "passive"))
      (node (ref "R1") (pin "1") (pinfunction "1_1") (pintype "passive"))
      (node (ref "U4") (pin "13") (pinfunction "G16_13") (pintype "input"))
    )
    (net (code "44") (name "Net-(U4-PD)") (class "Default")
      (node (ref "C43") (pin "2") (pinfunction "2_2") (pintype "passive"))
      (node (ref "C44") (pin "1") (pinfunction "1_1") (pintype "passive"))
      (node (ref "R14") (pin "2") (pinfunction "2_2") (pintype "passive"))
      (node (ref "R17") (pin "2") (pinfunction "2_2") (pintype "passive"))
      (node (ref "U4") (pin "6") (pinfunction "PD_6") (pintype "input"))
    )
    (net (code "45") (name "Net-(U5-J1)") (class "Default")
      (node (ref "C37") (pin "2") (pinfunction "2_2") (pintype "passive"))
      (node (ref "U5") (pin "5") (pinfunction "J1_5") (pintype "bidirectional"))
    )
    (net (code "46") (name "Net-(U5-J2)") (class "Default")
      (node (ref "C30") (pin "1") (pinfunction "1_1") (pintype "passive"))
      (node (ref "U5") (pin "3") (pinfunction "J2_3") (pintype "bidirectional"))
    )
    (net (code "47") (name "Net-(U5-J3)") (class "Default")
      (node (ref "C31") (pin "1") (pinfunction "1_1") (pintype "passive"))
      (node (ref "U5") (pin "1") (pinfunction "J3_1") (pintype "bidirectional"))
    )
    (net (code "48") (name "Net-(U7-HOLD)") (class "Default")
      (node (ref "C50") (pin "1") (pinfunction "1_1") (pintype "passive"))
      (node (ref "L1") (pin "1") (pinfunction "1_1") (pintype "passive"))
      (node (ref "U7") (pin "3") (pinfunction "WP_3") (pintype "bidirectional"))
      (node (ref "U7") (pin "7") (pinfunction "HOLD_7") (pintype "bidirectional"))
      (node (ref "U7") (pin "8") (pinfunction "VCC_8") (pintype "power_in"))
    )
    (net (code "49") (name "Net-(X1-OUT)") (class "Default")
      (node (ref "C17") (pin "1") (pinfunction "1_1") (pintype "passive"))
      (node (ref "X1") (pin "3") (pinfunction "OUT_3") (pintype "bidirectional"))
    )
    (net (code "50") (name "PA_PD") (class "Default")
      (node (ref "R17") (pin "1") (pinfunction "1_1") (pintype "passive"))
      (node (ref "U3") (pin "7") (pinfunction "GPIO7_7") (pintype "bidirectional"))
    )
    (net (code "51") (name "PROC_PWR_EN") (class "Default")
      (node (ref "IN") (pin "1") (pinfunction "1_1") (pintype "passive"))
      (node (ref "OUT") (pin "1") (pinfunction "1_1") (pintype "passive"))
    )
    (net (code "52") (name "RESETB") (class "Default")
      (node (ref "R8") (pin "2") (pinfunction "2_2") (pintype "passive"))
      (node (ref "U3") (pin "1") (pinfunction "RESETB_1") (pintype "bidirectional"))
      (node (ref "U8") (pin "1") (pinfunction "GPIO0_1") (pintype "bidirectional"))
    )
    (net (code "53") (name "RFG8") (class "Default")
      (node (ref "C22") (pin "2") (pinfunction "2_2") (pintype "passive"))
      (node (ref "K1") (pin "4") (pinfunction "DRAIN_2_4") (pintype "bidirectional"))
      (node (ref "R7") (pin "1") (pinfunction "1_1") (pintype "passive"))
      (node (ref "U4") (pin "12") (pinfunction "G8_12") (pintype "input"))
    )
    (net (code "54") (name "RF_RX") (class "Default")
      (node (ref "C29") (pin "P$2") (pinfunction "2_P$2") (pintype "passive"))
      (node (ref "C30") (pin "2") (pinfunction "2_2") (pintype "passive"))
      (node (ref "L12") (pin "P$2") (pinfunction "2_P$2") (pintype "passive"))
    )
    (net (code "55") (name "RF_TX") (class "Default")
      (node (ref "C28") (pin "2") (pinfunction "2_2") (pintype "passive"))
      (node (ref "C31") (pin "2") (pinfunction "2_2") (pintype "passive"))
      (node (ref "L8") (pin "P$2") (pinfunction "2_P$2") (pintype "passive"))
    )
    (net (code "56") (name "RXSW") (class "Default")
      (node (ref "C36") (pin "1") (pinfunction "1_1") (pintype "passive"))
      (node (ref "U3") (pin "22") (pinfunction "RXSW_22") (pintype "bidirectional"))
      (node (ref "U5") (pin "6") (pinfunction "V2_6") (pintype "power_in"))
    )
    (net (code "57") (name "SCL") (class "Default")
      (node (ref "IN") (pin "13") (pinfunction "13_13") (pintype "passive"))
      (node (ref "OUT") (pin "13") (pinfunction "13_13") (pintype "passive"))
      (node (ref "U8") (pin "6") (pinfunction "SCL_6") (pintype "bidirectional"))
    )
    (net (code "58") (name "SCLK") (class "Default")
      (node (ref "IN") (pin "4") (pinfunction "4_4") (pintype "passive"))
      (node (ref "OUT") (pin "4") (pinfunction "4_4") (pintype "passive"))
      (node (ref "U3") (pin "3") (pinfunction "SCLK_3") (pintype "bidirectional"))
    )
    (net (code "59") (name "SDA") (class "Default")
      (node (ref "IN") (pin "12") (pinfunction "12_12") (pintype "passive"))
      (node (ref "OUT") (pin "12") (pinfunction "12_12") (pintype "passive"))
      (node (ref "U8") (pin "7") (pinfunction "SDA_7") (pintype "bidirectional"))
    )
    (net (code "60") (name "TXSW") (class "Default")
      (node (ref "C42") (pin "1") (pinfunction "1_1") (pintype "passive"))
      (node (ref "U3") (pin "21") (pinfunction "TXSW_21") (pintype "bidirectional"))
      (node (ref "U5") (pin "4") (pinfunction "V1_4") (pintype "power_in"))
    )
    (net (code "61") (name "VDD") (class "Default")
      (node (ref "C14") (pin "1") (pinfunction "1_1") (pintype "passive"))
      (node (ref "C16") (pin "1") (pinfunction "1_1") (pintype "passive"))
      (node (ref "C19") (pin "1") (pinfunction "1_1") (pintype "passive"))
      (node (ref "C3") (pin "1") (pinfunction "1_1") (pintype "passive"))
      (node (ref "C45") (pin "1") (pinfunction "1_1") (pintype "passive"))
      (node (ref "C46") (pin "1") (pinfunction "1_1") (pintype "passive"))
      (node (ref "C49") (pin "1") (pinfunction "1_1") (pintype "passive"))
      (node (ref "C51") (pin "1") (pinfunction "1_1") (pintype "passive"))
      (node (ref "L1") (pin "2") (pinfunction "2_2") (pintype "passive"))
      (node (ref "L10") (pin "2") (pinfunction "2_2") (pintype "passive"))
      (node (ref "L15") (pin "2") (pinfunction "2_2") (pintype "passive"))
      (node (ref "L3") (pin "2") (pinfunction "2_2") (pintype "passive"))
      (node (ref "L6") (pin "P$1") (pinfunction "1_P$1") (pintype "passive"))
      (node (ref "Q2") (pin "2") (pinfunction "S_2") (pintype "bidirectional"))
      (node (ref "R3") (pin "2") (pinfunction "2_2") (pintype "passive"))
      (node (ref "U2") (pin "1") (pinfunction "IN_1") (pintype "input"))
      (node (ref "U2") (pin "3") (pinfunction "EN_3") (pintype "input"))
      (node (ref "U6") (pin "1") (pinfunction "IN_1") (pintype "input"))
      (node (ref "U6") (pin "3") (pinfunction "EN_3") (pintype "input"))
      (node (ref "U8") (pin "8") (pinfunction "VCC_8") (pintype "bidirectional"))
      (node (ref "VDD") (pin "1") (pinfunction "1_1") (pintype "bidirectional"))
    )
    (net (code "62") (name "VREF1") (class "Default")
      (node (ref "3V0") (pin "1") (pinfunction "1_1") (pintype "bidirectional"))
      (node (ref "C20") (pin "2") (pinfunction "2_2") (pintype "passive"))
      (node (ref "C21") (pin "2") (pinfunction "2_2") (pintype "passive"))
      (node (ref "G16") (pin "2") (pinfunction "2_2") (pintype "passive"))
      (node (ref "K1") (pin "3") (pinfunction "DRAIN_1_3") (pintype "bidirectional"))
      (node (ref "U4") (pin "16") (pinfunction "VBIAS_16") (pintype "power_in"))
      (node (ref "U6") (pin "5") (pinfunction "OUT_5") (pintype "passive"))
    )
    (net (code "63") (name "V_USB") (class "Default")
      (node (ref "IN") (pin "16") (pinfunction "16_16") (pintype "passive"))
      (node (ref "OUT") (pin "16") (pinfunction "16_16") (pintype "passive"))
    )
    (net (code "64") (name "unconnected-(OUT-Pad9)") (class "Default")
      (node (ref "OUT") (pin "9") (pinfunction "9_9") (pintype "passive"))
    )
    (net (code "65") (name "unconnected-(OUT-Pad11)") (class "Default")
      (node (ref "OUT") (pin "11") (pinfunction "11_11") (pintype "passive"))
    )
    (net (code "66") (name "unconnected-(U2-NC-Pad4)") (class "Default")
      (node (ref "U2") (pin "4") (pinfunction "NC_4") (pintype "no_connect"))
    )
    (net (code "67") (name "unconnected-(U3-GPIO0-Pad19)") (class "Default")
      (node (ref "U3") (pin "19") (pinfunction "GPIO0_19") (pintype "bidirectional"))
    )
    (net (code "68") (name "unconnected-(U3-GPIO1-Pad18)") (class "Default")
      (node (ref "U3") (pin "18") (pinfunction "GPIO1_18") (pintype "bidirectional"))
    )
    (net (code "69") (name "unconnected-(U3-GPIO2-Pad17)") (class "Default")
      (node (ref "U3") (pin "17") (pinfunction "GPIO2_17") (pintype "bidirectional"))
    )
    (net (code "70") (name "unconnected-(U3-GPIO3-Pad16)") (class "Default")
      (node (ref "U3") (pin "16") (pinfunction "GPIO3_16") (pintype "bidirectional"))
    )
    (net (code "71") (name "unconnected-(U3-GPIO4-Pad11)") (class "Default")
      (node (ref "U3") (pin "11") (pinfunction "GPIO4_11") (pintype "bidirectional"))
    )
    (net (code "72") (name "unconnected-(U3-GPIO5-Pad10)") (class "Default")
      (node (ref "U3") (pin "10") (pinfunction "GPIO5_10") (pintype "bidirectional"))
    )
    (net (code "73") (name "unconnected-(U3-GPIO6-Pad8)") (class "Default")
      (node (ref "U3") (pin "8") (pinfunction "GPIO6_8") (pintype "bidirectional"))
    )
    (net (code "74") (name "unconnected-(U3-INT2-Pad48)") (class "Default")
      (node (ref "U3") (pin "48") (pinfunction "INT2_48") (pintype "bidirectional"))
    )
    (net (code "75") (name "unconnected-(U3-NC-Pad42)") (class "Default")
      (node (ref "U3") (pin "42") (pinfunction "NC_42") (pintype "no_connect"))
    )
    (net (code "76") (name "unconnected-(U3-NC-Pad43)") (class "Default")
      (node (ref "U3") (pin "43") (pinfunction "NC_43") (pintype "no_connect"))
    )
    (net (code "77") (name "unconnected-(U3-NC-Pad44)") (class "Default")
      (node (ref "U3") (pin "44") (pinfunction "NC_44") (pintype "no_connect"))
    )
    (net (code "78") (name "unconnected-(U3-NC-Pad45)") (class "Default")
      (node (ref "U3") (pin "45") (pinfunction "NC_45") (pintype "no_connect"))
    )
    (net (code "79") (name "unconnected-(U4-NC-Pad1)") (class "Default")
      (node (ref "U4") (pin "1") (pinfunction "NC_1") (pintype "no_connect"))
    )
    (net (code "80") (name "unconnected-(U4-NC-Pad4)") (class "Default")
      (node (ref "U4") (pin "4") (pinfunction "NC_4") (pintype "no_connect"))
    )
    (net (code "81") (name "unconnected-(U4-NC-Pad5)") (class "Default")
      (node (ref "U4") (pin "5") (pinfunction "NC_5") (pintype "no_connect"))
    )
    (net (code "82") (name "unconnected-(U4-NC-Pad7)") (class "Default")
      (node (ref "U4") (pin "7") (pinfunction "NC_7") (pintype "no_connect"))
    )
    (net (code "83") (name "unconnected-(U4-NC-Pad8)") (class "Default")
      (node (ref "U4") (pin "8") (pinfunction "NC_8") (pintype "no_connect"))
    )
    (net (code "84") (name "unconnected-(U4-NC-Pad11)") (class "Default")
      (node (ref "U4") (pin "11") (pinfunction "NC_11") (pintype "no_connect"))
    )
    (net (code "85") (name "unconnected-(U4-NC-Pad15)") (class "Default")
      (node (ref "U4") (pin "15") (pinfunction "NC_15") (pintype "no_connect"))
    )
    (net (code "86") (name "unconnected-(U6-NC-Pad4)") (class "Default")
      (node (ref "U6") (pin "4") (pinfunction "NC_4") (pintype "no_connect"))
    )
  )
)
